# MCU_PROG.net
KiCad netlist of a schematic drawn in Altium Designer
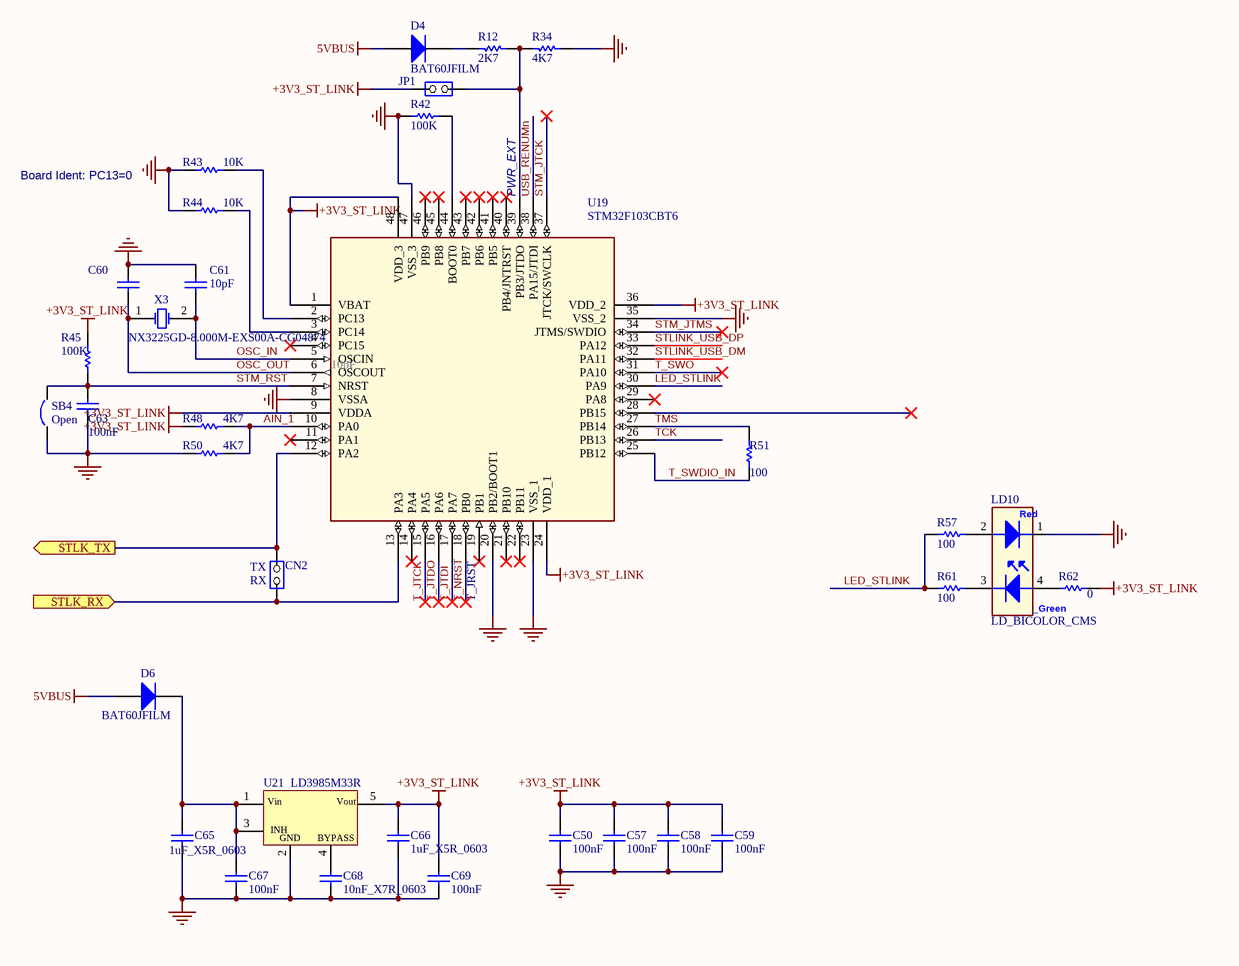
[diagram p0: MCU_PROG.SchDoc]

(export (version "E")
  (design (tool "Eeschema 10.0.6"))
  (components
    (comp (ref "C50")
      (value "100nF")
      (footprint "CAPC1608X90")
      (description "Capacitor 0402 / 0603 / 0805")
      (libsource (lib "MCD_TOOLS") (part "Capacitor_ST"))
    )
    (comp (ref "C57")
      (value "100nF")
      (footprint "CAPC1608X90")
      (description "Capacitor 0402 / 0603 / 0805")
      (libsource (lib "MCD_TOOLS") (part "Capacitor_ST"))
    )
    (comp (ref "C58")
      (value "100nF")
      (footprint "CAPC1608X90")
      (description "Capacitor 0402 / 0603 / 0805")
      (libsource (lib "MCD_TOOLS") (part "Capacitor_ST"))
    )
    (comp (ref "C59")
      (value "100nF")
      (footprint "CAPC1608X90")
      (description "Capacitor 0402 / 0603 / 0805")
      (libsource (lib "MCD_TOOLS") (part "Capacitor_ST"))
    )
    (comp (ref "C60")
      (value "10pF")
      (footprint "CAPC1608X90")
      (description "Capacitor 0402 / 0603 / 0805")
      (libsource (lib "MCD_TOOLS") (part "Capacitor_ST"))
    )
    (comp (ref "C61")
      (value "10pF")
      (footprint "CAPC1608X90")
      (description "Capacitor 0402 / 0603 / 0805")
      (libsource (lib "MCD_TOOLS") (part "Capacitor_ST"))
    )
    (comp (ref "C63")
      (value "100nF")
      (footprint "CAPC1608X90")
      (description "Capacitor 0402 / 0603 / 0805")
      (libsource (lib "MCD_TOOLS") (part "Capacitor_ST"))
    )
    (comp (ref "C65")
      (value "1uF_X5R_0603")
      (footprint "CAPC1608X90")
      (description "0603  X5R 1µF")
      (fields (field (name "TOLERANCE") "10%"))
      (libsource (lib "MB963_1") (part "CAP SMD 0603  X5R 1µF 25V 10%"))
    )
    (comp (ref "C66")
      (value "1uF_X5R_0603")
      (footprint "CAPC1608X90")
      (description "0603  X5R 1µF")
      (fields (field (name "TOLERANCE") "10%"))
      (libsource (lib "MB963_1") (part "CAP SMD 0603  X5R 1µF 25V 10%"))
    )
    (comp (ref "C67")
      (value "100nF")
      (footprint "CAPC1608X90")
      (description "Capacitor 0402 / 0603 / 0805")
      (libsource (lib "MCD_TOOLS") (part "Capacitor_ST"))
    )
    (comp (ref "C68")
      (value "10nF_X7R_0603")
      (footprint "CAPC1608X90")
      (description "0603  X7R 10NF")
      (fields (field (name "TOLERANCE") "10%"))
      (libsource (lib "MB963_1") (part "CAP SMD 0603  X7R 10000PF 50V 10%"))
    )
    (comp (ref "C69")
      (value "100nF")
      (footprint "CAPC1608X90")
      (description "Capacitor 0402 / 0603 / 0805")
      (libsource (lib "MCD_TOOLS") (part "Capacitor_ST"))
    )
    (comp (ref "CN2") (value "~") (footprint "HDR_1x2_2R54_V_M_S") (libsource (lib "MCD_TOOLS") (part "JP2")))
    (comp (ref "D4")
      (value "BAT60JFILM")
      (footprint "SOD-323")
      (description "Default Diode")
      (fields (field (name "PUBLISHER") "Altium Limited"))
      (libsource (lib "MB1144_1") (part "Diode"))
    )
    (comp (ref "D6")
      (value "BAT60JFILM")
      (footprint "SOD-323")
      (libsource (lib "MB1137") (part "BAT60JFILM"))
    )
    (comp (ref "JP1") (value "~") (footprint "HDR_1x2_2R54_V_M_S") (libsource (lib "*") (part "JP2")))
    (comp (ref "LD10")
      (value "LD_BICOLOR_CMS")
      (footprint "LED_201-A00J1_BRA")
      (description "Bicolor Led")
      (libsource (lib "MB1137") (part "LD_BICOLOR_CMS"))
    )
    (comp (ref "R12")
      (value "2K7")
      (footprint "R0603")
      (description "Resistor")
      (fields (field (name "PUBLISHER") "Altium Limited"))
      (libsource (lib "") (part "Res1_1"))
    )
    (comp (ref "R34")
      (value "4K7")
      (footprint "RESC1607X60N")
      (description "Resistor")
      (fields (field (name "PUBLISHER") "Altium Limited"))
      (libsource (lib "") (part "Res1_1"))
    )
    (comp (ref "R42")
      (value "100K")
      (footprint "RESC1607X60N")
      (description "Resistor 0402 / 0603 / 0805")
      (libsource (lib "Miscellaneous Devices") (part "Res1"))
    )
    (comp (ref "R43")
      (value "10K")
      (footprint "RESC1608X55")
      (description "Resistor 0402 / 0603 / 0805")
      (libsource (lib "Miscellaneous Devices") (part "Res1"))
    )
    (comp (ref "R44")
      (value "10K")
      (footprint "RESC1607X60N")
      (description "Resistor 0402 / 0603 / 0805")
      (libsource (lib "Miscellaneous Devices") (part "Res1"))
    )
    (comp (ref "R45")
      (value "100K")
      (footprint "RESC1607X60N")
      (description "Resistor 0402 / 0603 / 0805")
      (libsource (lib "Miscellaneous Devices") (part "Res1"))
    )
    (comp (ref "R48")
      (value "4K7")
      (footprint "RESC1607X60N")
      (description "Resistor 0402 / 0603 / 0805")
      (libsource (lib "Miscellaneous Devices") (part "Res1"))
    )
    (comp (ref "R50")
      (value "4K7")
      (footprint "RESC1607X60N")
      (description "Resistor 0402 / 0603 / 0805")
      (libsource (lib "Miscellaneous Devices") (part "Res1"))
    )
    (comp (ref "R51")
      (value "100")
      (footprint "RESC1607X60N")
      (description "Resistor 0402 / 0603 / 0805")
      (libsource (lib "Miscellaneous Devices") (part "Res1"))
    )
    (comp (ref "R57")
      (value "100")
      (footprint "RESC1607X60N")
      (description "Resistor 0402 / 0603 / 0805")
      (libsource (lib "Miscellaneous Devices") (part "Res1"))
    )
    (comp (ref "R61")
      (value "100")
      (footprint "RESC1607X60N")
      (description "Resistor 0402 / 0603 / 0805")
      (libsource (lib "Miscellaneous Devices") (part "Res1"))
    )
    (comp (ref "R62")
      (value "0")
      (footprint "RESC1607X60N")
      (description "Resistor 0402 / 0603 / 0805")
      (libsource (lib "Miscellaneous Devices") (part "Res1"))
    )
    (comp (ref "SB4")
      (value "Open")
      (footprint "SB_0603")
      (description "Circuit Breaker")
      (fields (field (name "PUBLISHER") "Altium Limited"))
      (libsource (lib "MB1167") (part "Circuit Breaker"))
    )
    (comp (ref "U19")
      (value "STM32F103CBT6")
      (footprint "QFP50P900X900X160-48N")
      (description "Medium-density performance line ARM-based 32-bit MCU with 64KB Flash")
      (libsource (lib "Nucleo_64") (part "STM32F103CBT6"))
    )
    (comp (ref "U21")
      (value "LD3985M33R")
      (footprint "SOT95P280X145-5N")
      (description "Ultra low drop-low noise BiCMOS voltage, regulators low ESR capacitors compatible")
      (libsource (lib "MCD_TOOLS") (part "LD3985M33R"))
    )
    (comp (ref "X3")
      (value "NX3225GD-8.000M-EXS00A-CG04874")
      (footprint "XTAL_NX3225GD_NDK-L")
      (description "Crystal Oscillator")
      (fields (field (name "PUBLISHER") "Altium Limited"))
      (libsource (lib "MB963_1") (part "XTAL"))
    )
  )
  (nets
    (net (code "1") (name "+3V3_ST_LINK") (class "Default")
      (node (ref "C50") (pin "2") (pinfunction "2_2") (pintype "passive"))
      (node (ref "C57") (pin "2") (pinfunction "2_2") (pintype "passive"))
      (node (ref "C58") (pin "2") (pinfunction "2_2") (pintype "passive"))
      (node (ref "C59") (pin "2") (pinfunction "2_2") (pintype "passive"))
      (node (ref "C66") (pin "1") (pinfunction "1_1") (pintype "passive"))
      (node (ref "C69") (pin "2") (pinfunction "2_2") (pintype "passive"))
      (node (ref "JP1") (pin "1") (pinfunction "COMMON_1") (pintype "passive"))
      (node (ref "R45") (pin "2") (pinfunction "2_2") (pintype "passive"))
      (node (ref "R48") (pin "1") (pinfunction "1_1") (pintype "passive"))
      (node (ref "R62") (pin "2") (pinfunction "2_2") (pintype "passive"))
      (node (ref "U19") (pin "1") (pinfunction "VBAT_1") (pintype "power_in"))
      (node (ref "U19") (pin "24") (pinfunction "VDD_1_24") (pintype "power_in"))
      (node (ref "U19") (pin "36") (pinfunction "VDD_2_36") (pintype "power_in"))
      (node (ref "U19") (pin "48") (pinfunction "VDD_3_48") (pintype "power_in"))
      (node (ref "U19") (pin "9") (pinfunction "VDDA_9") (pintype "power_in"))
      (node (ref "U21") (pin "5") (pinfunction "Vout_5") (pintype "passive"))
    )
    (net (code "2") (name "/AIN_1") (class "Default")
      (node (ref "R48") (pin "2") (pinfunction "2_2") (pintype "passive"))
      (node (ref "R50") (pin "2") (pinfunction "2_2") (pintype "passive"))
      (node (ref "U19") (pin "10") (pinfunction "PA0_10") (pintype "bidirectional"))
    )
    (net (code "3") (name "/LED_STLINK") (class "Default")
      (node (ref "R57") (pin "1") (pinfunction "1_1") (pintype "passive"))
      (node (ref "R61") (pin "1") (pinfunction "1_1") (pintype "passive"))
      (node (ref "U19") (pin "30") (pinfunction "PA9_30") (pintype "bidirectional"))
    )
    (net (code "4") (name "/OSC_IN") (class "Default")
      (node (ref "C61") (pin "1") (pinfunction "1_1") (pintype "passive"))
      (node (ref "U19") (pin "5") (pinfunction "OSCIN_5") (pintype "input"))
      (node (ref "X3") (pin "2") (pinfunction "OSC2_2") (pintype "passive"))
    )
    (net (code "5") (name "/OSC_OUT") (class "Default")
      (node (ref "C60") (pin "1") (pinfunction "1_1") (pintype "passive"))
      (node (ref "U19") (pin "6") (pinfunction "OSCOUT_6") (pintype "output"))
      (node (ref "X3") (pin "1") (pinfunction "OSC1_1") (pintype "passive"))
    )
    (net (code "6") (name "/STLINK_USB_DM") (class "Default")
      (node (ref "U19") (pin "32") (pinfunction "PA11_32") (pintype "bidirectional"))
    )
    (net (code "7") (name "/STLINK_USB_DP") (class "Default")
      (node (ref "U19") (pin "33") (pinfunction "PA12_33") (pintype "bidirectional"))
    )
    (net (code "8") (name "/STLK_RX") (class "Default")
      (node (ref "CN2") (pin "1") (pinfunction "COMMON_1") (pintype "passive"))
      (node (ref "U19") (pin "13") (pinfunction "PA3_13") (pintype "bidirectional"))
    )
    (net (code "9") (name "/STLK_TX") (class "Default")
      (node (ref "CN2") (pin "2") (pinfunction "NO_2") (pintype "passive"))
      (node (ref "U19") (pin "12") (pinfunction "PA2_12") (pintype "bidirectional"))
    )
    (net (code "10") (name "/STM_JTCK") (class "Default")
      (node (ref "U19") (pin "37") (pinfunction "JTCK/SWCLK_37") (pintype "bidirectional+no_connect"))
    )
    (net (code "11") (name "/STM_JTMS") (class "Default")
      (node (ref "U19") (pin "34") (pinfunction "JTMS/SWDIO_34") (pintype "bidirectional+no_connect"))
    )
    (net (code "12") (name "/STM_RST") (class "Default")
      (node (ref "C63") (pin "2") (pinfunction "2_2") (pintype "passive"))
      (node (ref "R45") (pin "1") (pinfunction "1_1") (pintype "passive"))
      (node (ref "SB4") (pin "2") (pinfunction "2_2") (pintype "passive"))
      (node (ref "U19") (pin "7") (pinfunction "NRST_7") (pintype "input"))
    )
    (net (code "13") (name "/TCK") (class "Default")
      (node (ref "U19") (pin "26") (pinfunction "PB13_26") (pintype "bidirectional"))
    )
    (net (code "14") (name "/TMS") (class "Default")
      (node (ref "R51") (pin "2") (pinfunction "2_2") (pintype "passive"))
      (node (ref "U19") (pin "27") (pinfunction "PB14_27") (pintype "bidirectional"))
    )
    (net (code "15") (name "/T_JTCK") (class "Default")
      (node (ref "U19") (pin "15") (pinfunction "PA5_15") (pintype "bidirectional+no_connect"))
    )
    (net (code "16") (name "/T_JTDI") (class "Default")
      (node (ref "U19") (pin "17") (pinfunction "PA7_17") (pintype "bidirectional+no_connect"))
    )
    (net (code "17") (name "/T_JTDO") (class "Default")
      (node (ref "U19") (pin "16") (pinfunction "PA6_16") (pintype "bidirectional+no_connect"))
    )
    (net (code "18") (name "/T_NRST") (class "Default")
      (node (ref "U19") (pin "18") (pinfunction "PB0_18") (pintype "bidirectional+no_connect"))
    )
    (net (code "19") (name "/T_SWDIO_IN") (class "Default")
      (node (ref "R51") (pin "1") (pinfunction "1_1") (pintype "passive"))
      (node (ref "U19") (pin "25") (pinfunction "PB12_25") (pintype "bidirectional"))
    )
    (net (code "20") (name "/T_SWO") (class "Default")
      (node (ref "U19") (pin "31") (pinfunction "PA10_31") (pintype "bidirectional+no_connect"))
    )
    (net (code "21") (name "/USB_RENUMn") (class "Default")
      (node (ref "U19") (pin "38") (pinfunction "PA15/JTDI_38") (pintype "bidirectional"))
    )
    (net (code "22") (name "5VBUS") (class "Default")
      (node (ref "D4") (pin "1") (pinfunction "A_1") (pintype "passive"))
      (node (ref "D6") (pin "1") (pinfunction "A_1") (pintype "passive"))
    )
    (net (code "23") (name "GND") (class "Default")
      (node (ref "C50") (pin "1") (pinfunction "1_1") (pintype "passive"))
      (node (ref "C57") (pin "1") (pinfunction "1_1") (pintype "passive"))
      (node (ref "C58") (pin "1") (pinfunction "1_1") (pintype "passive"))
      (node (ref "C59") (pin "1") (pinfunction "1_1") (pintype "passive"))
      (node (ref "C60") (pin "2") (pinfunction "2_2") (pintype "passive"))
      (node (ref "C61") (pin "2") (pinfunction "2_2") (pintype "passive"))
      (node (ref "C63") (pin "1") (pinfunction "1_1") (pintype "passive"))
      (node (ref "C65") (pin "1") (pinfunction "1_1") (pintype "passive"))
      (node (ref "C66") (pin "2") (pinfunction "2_2") (pintype "passive"))
      (node (ref "C67") (pin "1") (pinfunction "1_1") (pintype "passive"))
      (node (ref "C68") (pin "1") (pinfunction "1_1") (pintype "passive"))
      (node (ref "C69") (pin "1") (pinfunction "1_1") (pintype "passive"))
      (node (ref "LD10") (pin "1") (pinfunction "1_1") (pintype "passive"))
      (node (ref "R34") (pin "2") (pinfunction "2_2") (pintype "passive"))
      (node (ref "R42") (pin "1") (pinfunction "1_1") (pintype "passive"))
      (node (ref "R43") (pin "1") (pinfunction "1_1") (pintype "passive"))
      (node (ref "R44") (pin "1") (pinfunction "1_1") (pintype "passive"))
      (node (ref "R50") (pin "1") (pinfunction "1_1") (pintype "passive"))
      (node (ref "SB4") (pin "1") (pinfunction "1_1") (pintype "passive"))
      (node (ref "U19") (pin "20") (pinfunction "PB2/BOOT1_20") (pintype "bidirectional"))
      (node (ref "U19") (pin "23") (pinfunction "VSS_1_23") (pintype "power_in"))
      (node (ref "U19") (pin "35") (pinfunction "VSS_2_35") (pintype "power_in"))
      (node (ref "U19") (pin "47") (pinfunction "VSS_3_47") (pintype "power_in"))
      (node (ref "U19") (pin "8") (pinfunction "VSSA_8") (pintype "power_in"))
      (node (ref "U21") (pin "2") (pinfunction "GND_2") (pintype "passive"))
    )
    (net (code "24") (name "Net-(D4-K)") (class "Default")
      (node (ref "D4") (pin "2") (pinfunction "K_2") (pintype "passive"))
      (node (ref "R12") (pin "1") (pinfunction "1_1") (pintype "passive"))
    )
    (net (code "25") (name "Net-(D6-K)") (class "Default")
      (node (ref "C65") (pin "2") (pinfunction "2_2") (pintype "passive"))
      (node (ref "C67") (pin "2") (pinfunction "2_2") (pintype "passive"))
      (node (ref "D6") (pin "2") (pinfunction "K_2") (pintype "passive"))
      (node (ref "U21") (pin "1") (pinfunction "Vin_1") (pintype "passive"))
      (node (ref "U21") (pin "3") (pinfunction "CE_3") (pintype "passive"))
    )
    (net (code "26") (name "Net-(JP1-NO)") (class "Default")
      (node (ref "JP1") (pin "2") (pinfunction "NO_2") (pintype "passive"))
      (node (ref "R12") (pin "2") (pinfunction "2_2") (pintype "passive"))
      (node (ref "R34") (pin "1") (pinfunction "1_1") (pintype "passive"))
      (node (ref "U19") (pin "39") (pinfunction "PB3/JTDO_39") (pintype "bidirectional"))
    )
    (net (code "27") (name "Net-(LD10-Pad2)") (class "Default")
      (node (ref "LD10") (pin "2") (pinfunction "2_2") (pintype "passive"))
      (node (ref "R57") (pin "2") (pinfunction "2_2") (pintype "passive"))
    )
    (net (code "28") (name "Net-(LD10-Pad3)") (class "Default")
      (node (ref "LD10") (pin "3") (pinfunction "3_3") (pintype "passive"))
      (node (ref "R61") (pin "2") (pinfunction "2_2") (pintype "passive"))
    )
    (net (code "29") (name "Net-(LD10-Pad4)") (class "Default")
      (node (ref "LD10") (pin "4") (pinfunction "4_4") (pintype "passive"))
      (node (ref "R62") (pin "1") (pinfunction "1_1") (pintype "passive"))
    )
    (net (code "30") (name "Net-(U19-BOOT0)") (class "Default")
      (node (ref "R42") (pin "2") (pinfunction "2_2") (pintype "passive"))
      (node (ref "U19") (pin "44") (pinfunction "BOOT0_44") (pintype "bidirectional"))
    )
    (net (code "31") (name "Net-(U19-PC13)") (class "Default")
      (node (ref "R43") (pin "2") (pinfunction "2_2") (pintype "passive"))
      (node (ref "U19") (pin "2") (pinfunction "PC13_2") (pintype "bidirectional"))
    )
    (net (code "32") (name "Net-(U19-PC14)") (class "Default")
      (node (ref "R44") (pin "2") (pinfunction "2_2") (pintype "passive"))
      (node (ref "U19") (pin "3") (pinfunction "PC14_3") (pintype "bidirectional"))
    )
    (net (code "33") (name "Net-(U21-BYPASS)") (class "Default")
      (node (ref "C68") (pin "2") (pinfunction "2_2") (pintype "passive"))
      (node (ref "U21") (pin "4") (pinfunction "BYPASS_4") (pintype "passive"))
    )
    (net (code "34") (name "unconnected-(U19-PA1-Pad11)") (class "Default")
      (node (ref "U19") (pin "11") (pinfunction "PA1_11") (pintype "bidirectional+no_connect"))
    )
    (net (code "35") (name "unconnected-(U19-PA4-Pad14)") (class "Default")
      (node (ref "U19") (pin "14") (pinfunction "PA4_14") (pintype "bidirectional+no_connect"))
    )
    (net (code "36") (name "unconnected-(U19-PA8-Pad29)") (class "Default")
      (node (ref "U19") (pin "29") (pinfunction "PA8_29") (pintype "bidirectional+no_connect"))
    )
    (net (code "37") (name "unconnected-(U19-PB1-Pad19)") (class "Default")
      (node (ref "U19") (pin "19") (pinfunction "PB1_19") (pintype "input+no_connect"))
    )
    (net (code "38") (name "unconnected-(U19-PB4{slash}JNTRST-Pad40)") (class "Default")
      (node (ref "U19") (pin "40") (pinfunction "PB4/JNTRST_40") (pintype "bidirectional+no_connect"))
    )
    (net (code "39") (name "unconnected-(U19-PB5-Pad41)") (class "Default")
      (node (ref "U19") (pin "41") (pinfunction "PB5_41") (pintype "bidirectional+no_connect"))
    )
    (net (code "40") (name "unconnected-(U19-PB6-Pad42)") (class "Default")
      (node (ref "U19") (pin "42") (pinfunction "PB6_42") (pintype "bidirectional+no_connect"))
    )
    (net (code "41") (name "unconnected-(U19-PB7-Pad43)") (class "Default")
      (node (ref "U19") (pin "43") (pinfunction "PB7_43") (pintype "bidirectional+no_connect"))
    )
    (net (code "42") (name "unconnected-(U19-PB8-Pad45)") (class "Default")
      (node (ref "U19") (pin "45") (pinfunction "PB8_45") (pintype "bidirectional+no_connect"))
    )
    (net (code "43") (name "unconnected-(U19-PB9-Pad46)") (class "Default")
      (node (ref "U19") (pin "46") (pinfunction "PB9_46") (pintype "bidirectional+no_connect"))
    )
    (net (code "44") (name "unconnected-(U19-PB10-Pad21)") (class "Default")
      (node (ref "U19") (pin "21") (pinfunction "PB10_21") (pintype "bidirectional+no_connect"))
    )
    (net (code "45") (name "unconnected-(U19-PB11-Pad22)") (class "Default")
      (node (ref "U19") (pin "22") (pinfunction "PB11_22") (pintype "bidirectional+no_connect"))
    )
    (net (code "46") (name "unconnected-(U19-PB15-Pad28)") (class "Default")
      (node (ref "U19") (pin "28") (pinfunction "PB15_28") (pintype "bidirectional+no_connect"))
    )
    (net (code "47") (name "unconnected-(U19-PC15-Pad4)") (class "Default")
      (node (ref "U19") (pin "4") (pinfunction "PC15_4") (pintype "bidirectional+no_connect"))
    )
  )
)
